# STORAGE.net
KiCad netlist of a schematic drawn in Altium Designer
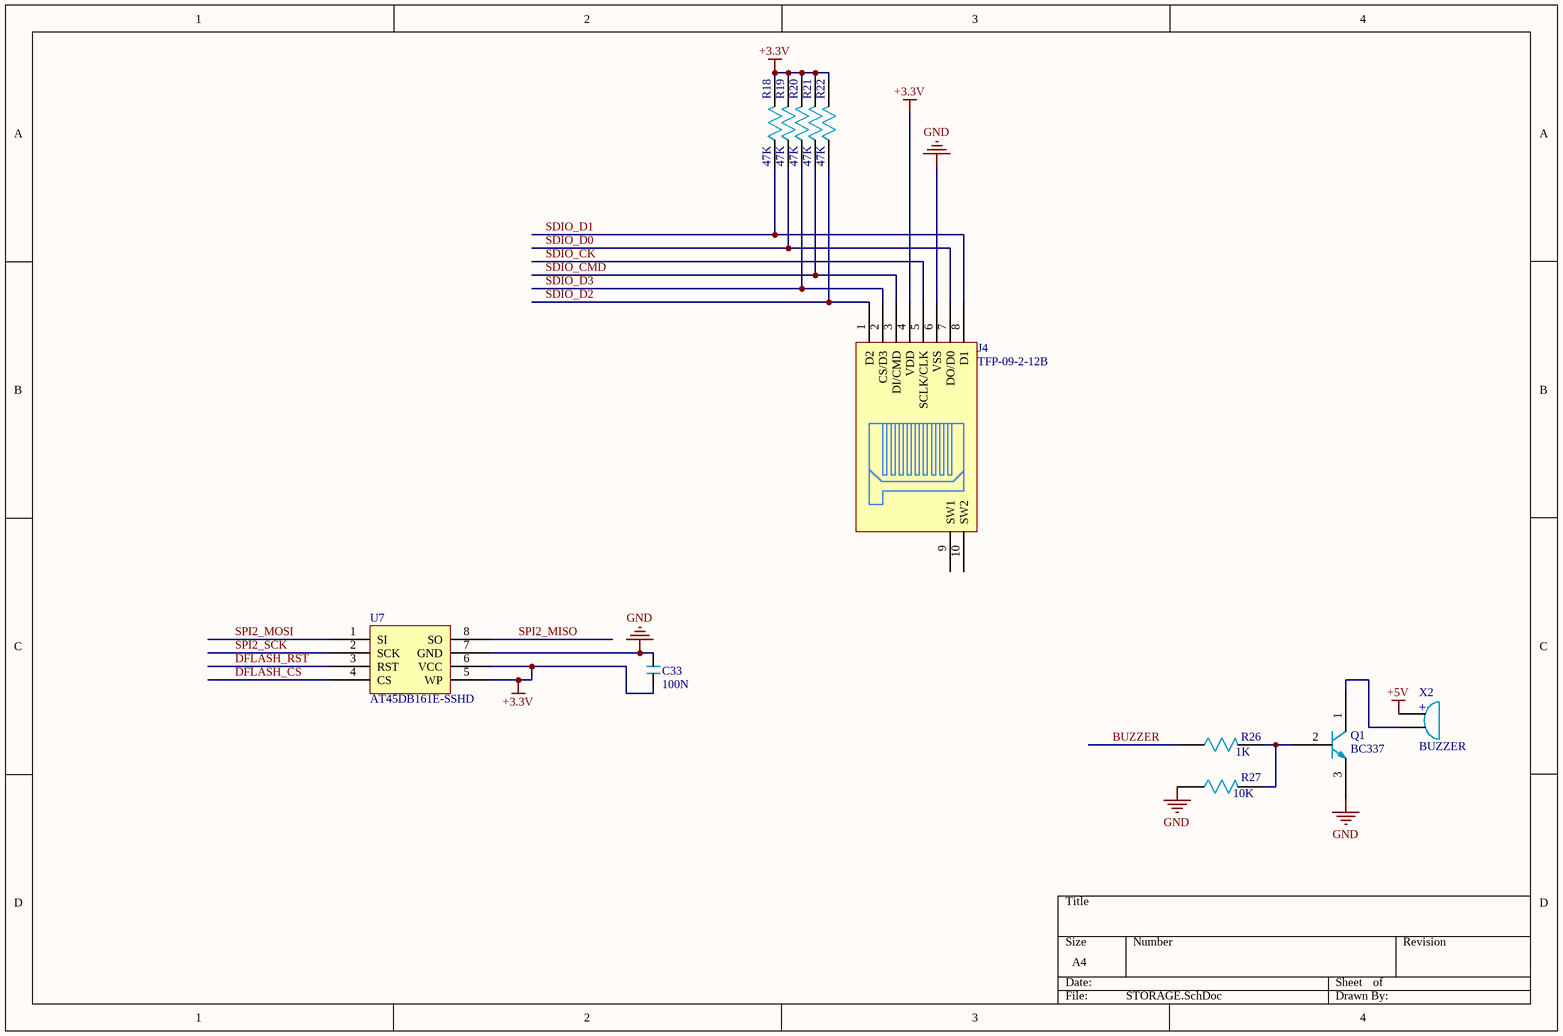
[diagram p0: STORAGE.SchDoc]

(export (version "E")
  (design (tool "Eeschema 10.0.6"))
  (components
    (comp (ref "C33") (value "100N") (footprint "0603") (libsource (lib "R_L_C_V") (part "CAP")))
    (comp (ref "J4")
      (value "TFP-09-2-12B")
      (footprint "TFP-09-2-12B")
      (libsource (lib "CONNECTOR") (part "uSD"))
    )
    (comp (ref "Q1") (value "BC337") (footprint "BC337") (libsource (lib "TRANSISTORS") (part "NPN-SMD")))
    (comp (ref "R18")
      (value "47K")
      (footprint "0603")
      (description "RES")
      (libsource (lib "R_L_C_V") (part "RES"))
    )
    (comp (ref "R19")
      (value "47K")
      (footprint "0603")
      (description "RES")
      (libsource (lib "R_L_C_V") (part "RES"))
    )
    (comp (ref "R20")
      (value "47K")
      (footprint "0603")
      (description "RES")
      (libsource (lib "R_L_C_V") (part "RES"))
    )
    (comp (ref "R21")
      (value "47K")
      (footprint "0603")
      (description "RES")
      (libsource (lib "R_L_C_V") (part "RES"))
    )
    (comp (ref "R22")
      (value "47K")
      (footprint "0603")
      (description "RES")
      (libsource (lib "R_L_C_V") (part "RES"))
    )
    (comp (ref "R26") (value "1K") (footprint "0603") (libsource (lib "My_lib") (part "RES")))
    (comp (ref "R27") (value "10K") (footprint "0603") (libsource (lib "My_lib") (part "RES")))
    (comp (ref "U7")
      (value "AT45DB161E-SSHD")
      (footprint "8S2")
      (libsource (lib "MY_IC") (part "AT45DB161E-SSHD"))
    )
    (comp (ref "X2") (value "BUZZER") (footprint "BUZZER") (libsource (lib "My_lib") (part "BUZZER")))
  )
  (nets
    (net (code "1") (name "+3.3V") (class "Default")
      (node (ref "C33") (pin "2") (pintype "passive"))
      (node (ref "J4") (pin "4") (pinfunction "VDD_4") (pintype "passive"))
      (node (ref "R18") (pin "2") (pintype "passive"))
      (node (ref "R19") (pin "2") (pintype "passive"))
      (node (ref "R20") (pin "2") (pintype "passive"))
      (node (ref "R21") (pin "2") (pintype "passive"))
      (node (ref "R22") (pin "2") (pintype "passive"))
      (node (ref "U7") (pin "5") (pinfunction "WP_5") (pintype "passive"))
      (node (ref "U7") (pin "6") (pinfunction "VCC_6") (pintype "passive"))
    )
    (net (code "2") (name "+5V") (class "Default")
      (node (ref "X2") (pin "1") (pinfunction "VCC_1") (pintype "passive"))
    )
    (net (code "3") (name "/BUZZER") (class "Default") (node (ref "R26") (pin "1") (pintype "passive")))
    (net (code "4") (name "/DFLASH_CS") (class "Default")
      (node (ref "U7") (pin "4") (pinfunction "CS_4") (pintype "passive"))
    )
    (net (code "5") (name "/DFLASH_RST") (class "Default")
      (node (ref "U7") (pin "3") (pinfunction "RST_3") (pintype "passive"))
    )
    (net (code "6") (name "/SDIO_CK") (class "Default")
      (node (ref "J4") (pin "5") (pinfunction "SCLK/CLK_5") (pintype "passive"))
    )
    (net (code "7") (name "/SDIO_CMD") (class "Default")
      (node (ref "J4") (pin "3") (pinfunction "DI/CMD_3") (pintype "passive"))
      (node (ref "R21") (pin "1") (pintype "passive"))
    )
    (net (code "8") (name "/SDIO_D0") (class "Default")
      (node (ref "J4") (pin "7") (pinfunction "DO/D0_7") (pintype "passive"))
      (node (ref "R19") (pin "1") (pintype "passive"))
    )
    (net (code "9") (name "/SDIO_D1") (class "Default")
      (node (ref "J4") (pin "8") (pinfunction "D1_8") (pintype "passive"))
      (node (ref "R18") (pin "1") (pintype "passive"))
    )
    (net (code "10") (name "/SDIO_D2") (class "Default")
      (node (ref "J4") (pin "1") (pinfunction "D2_1") (pintype "passive"))
      (node (ref "R22") (pin "1") (pintype "passive"))
    )
    (net (code "11") (name "/SDIO_D3") (class "Default")
      (node (ref "J4") (pin "2") (pinfunction "CS/D3_2") (pintype "passive"))
      (node (ref "R20") (pin "1") (pintype "passive"))
    )
    (net (code "12") (name "/SPI2_MISO") (class "Default")
      (node (ref "U7") (pin "8") (pinfunction "SO_8") (pintype "passive"))
    )
    (net (code "13") (name "/SPI2_MOSI") (class "Default")
      (node (ref "U7") (pin "1") (pinfunction "SI_1") (pintype "passive"))
    )
    (net (code "14") (name "/SPI2_SCK") (class "Default")
      (node (ref "U7") (pin "2") (pinfunction "SCK_2") (pintype "passive"))
    )
    (net (code "15") (name "GND") (class "Default")
      (node (ref "C33") (pin "1") (pintype "passive"))
      (node (ref "J4") (pin "6") (pinfunction "VSS_6") (pintype "passive"))
      (node (ref "Q1") (pin "3") (pintype "passive"))
      (node (ref "R27") (pin "1") (pintype "passive"))
      (node (ref "U7") (pin "7") (pinfunction "GND_7") (pintype "passive"))
    )
    (net (code "16") (name "Net-(Q1-Pad2)") (class "Default")
      (node (ref "Q1") (pin "2") (pintype "passive"))
      (node (ref "R26") (pin "2") (pintype "passive"))
      (node (ref "R27") (pin "2") (pintype "passive"))
    )
    (net (code "17") (name "Net-(X2-GND)") (class "Default")
      (node (ref "Q1") (pin "1") (pintype "passive"))
      (node (ref "X2") (pin "2") (pinfunction "GND_2") (pintype "passive"))
    )
    (net (code "18") (name "unconnected-(J4-SW1-Pad9)") (class "Default")
      (node (ref "J4") (pin "9") (pinfunction "SW1_9") (pintype "passive"))
    )
    (net (code "19") (name "unconnected-(J4-SW2-Pad10)") (class "Default")
      (node (ref "J4") (pin "10") (pinfunction "SW2_10") (pintype "passive"))
    )
  )
)
